# LEDControlSchaltPlan.net
KiCad netlist of a schematic drawn in EAGLE
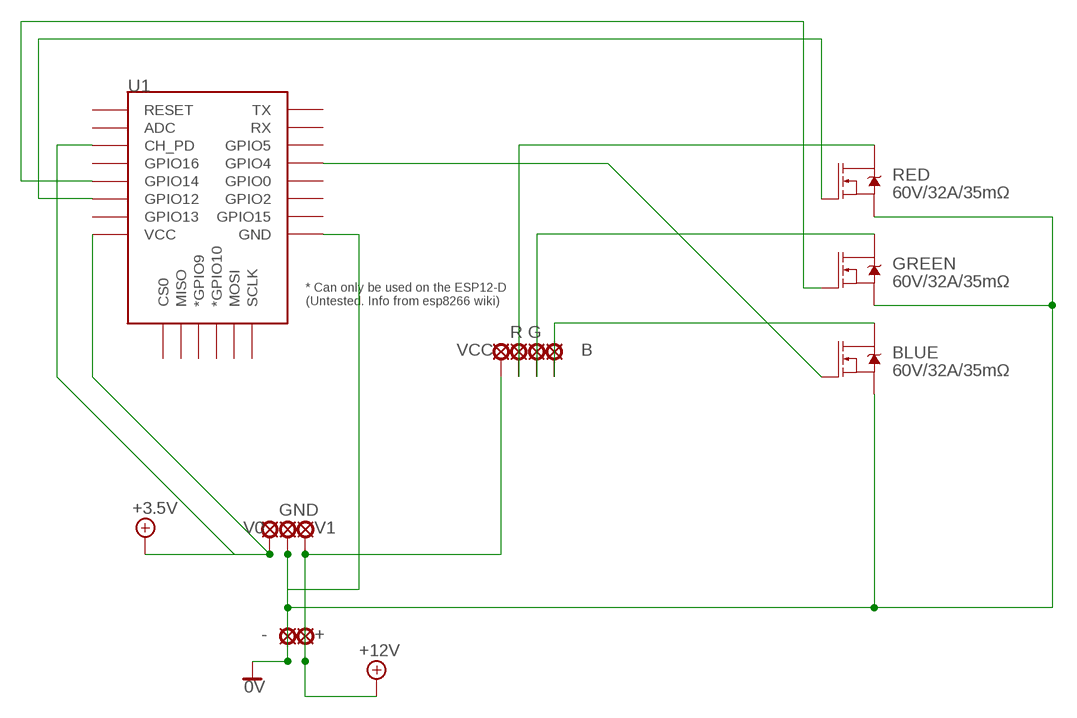
[diagram p0: schematic, sheet 1]

(export (version "E")
  (design (tool "Eeschema 10.0.6"))
  (components
    (comp (ref "+")
      (value "LSP10")
      (footprint "eagle-import:LSP10")
      (libsource (lib "eagle-import") (part "LSP10"))
    )
    (comp (ref "-")
      (value "LSP10")
      (footprint "eagle-import:LSP10")
      (libsource (lib "eagle-import") (part "LSP10"))
    )
    (comp (ref "B")
      (value "LSP10")
      (footprint "eagle-import:LSP10")
      (libsource (lib "eagle-import") (part "LSP10"))
    )
    (comp (ref "BLUE")
      (value "60V/32A/35mΩ")
      (footprint "eagle-import:TO220V")
      (libsource (lib "eagle-import") (part "MOSFET-NCH-FQP30N06L"))
    )
    (comp (ref "G")
      (value "LSP10")
      (footprint "eagle-import:LSP10")
      (libsource (lib "eagle-import") (part "LSP10"))
    )
    (comp (ref "GND")
      (value "LSP10")
      (footprint "eagle-import:LSP10")
      (libsource (lib "eagle-import") (part "LSP10"))
    )
    (comp (ref "GREEN")
      (value "60V/32A/35mΩ")
      (footprint "eagle-import:TO220V")
      (libsource (lib "eagle-import") (part "MOSFET-NCH-FQP30N06L"))
    )
    (comp (ref "R")
      (value "LSP10")
      (footprint "eagle-import:LSP10")
      (libsource (lib "eagle-import") (part "LSP10"))
    )
    (comp (ref "RED")
      (value "60V/32A/35mΩ")
      (footprint "eagle-import:TO220V")
      (libsource (lib "eagle-import") (part "MOSFET-NCH-FQP30N06L"))
    )
    (comp (ref "U1")
      (value "ESP12ESMD")
      (footprint "eagle-import:ESP12E-SMD")
      (libsource (lib "eagle-import") (part "ESP12ESMD"))
    )
    (comp (ref "V0")
      (value "LSP10")
      (footprint "eagle-import:LSP10")
      (libsource (lib "eagle-import") (part "LSP10"))
    )
    (comp (ref "V1")
      (value "LSP10")
      (footprint "eagle-import:LSP10")
      (libsource (lib "eagle-import") (part "LSP10"))
    )
    (comp (ref "VCC")
      (value "LSP10")
      (footprint "eagle-import:LSP10")
      (libsource (lib "eagle-import") (part "LSP10"))
    )
  )
  (nets
    (net (code "1") (name "+3.5V") (class "Default")
      (node (ref "U1") (pin "CH_PD") (pinfunction "CH_PD_CH_PD") (pintype "bidirectional"))
      (node (ref "U1") (pin "VCC") (pinfunction "VCC_VCC") (pintype "bidirectional"))
      (node (ref "V0") (pin "MP") (pinfunction "MP_MP") (pintype "passive"))
    )
    (net (code "2") (name "+12V") (class "Default")
      (node (ref "+") (pin "MP") (pinfunction "MP_MP") (pintype "passive"))
      (node (ref "V1") (pin "MP") (pinfunction "MP_MP") (pintype "passive"))
      (node (ref "VCC") (pin "MP") (pinfunction "MP_MP") (pintype "passive"))
    )
    (net (code "3") (name "0V") (class "Default")
      (node (ref "-") (pin "MP") (pinfunction "MP_MP") (pintype "passive"))
      (node (ref "BLUE") (pin "3") (pinfunction "S_3") (pintype "bidirectional"))
      (node (ref "GND") (pin "MP") (pinfunction "MP_MP") (pintype "passive"))
      (node (ref "GREEN") (pin "3") (pinfunction "S_3") (pintype "bidirectional"))
      (node (ref "RED") (pin "3") (pinfunction "S_3") (pintype "bidirectional"))
      (node (ref "U1") (pin "GND") (pinfunction "GND_GND") (pintype "bidirectional"))
    )
    (net (code "4") (name "Net-(BLUE-D)") (class "Default")
      (node (ref "B") (pin "MP") (pinfunction "MP_MP") (pintype "passive"))
      (node (ref "BLUE") (pin "2") (pinfunction "D_2") (pintype "bidirectional"))
    )
    (net (code "5") (name "Net-(BLUE-G)") (class "Default")
      (node (ref "BLUE") (pin "1") (pinfunction "G_1") (pintype "bidirectional"))
      (node (ref "U1") (pin "GPIO4") (pinfunction "GPIO4_GPIO4") (pintype "bidirectional"))
    )
    (net (code "6") (name "Net-(GREEN-D)") (class "Default")
      (node (ref "G") (pin "MP") (pinfunction "MP_MP") (pintype "passive"))
      (node (ref "GREEN") (pin "2") (pinfunction "D_2") (pintype "bidirectional"))
    )
    (net (code "7") (name "Net-(GREEN-G)") (class "Default")
      (node (ref "GREEN") (pin "1") (pinfunction "G_1") (pintype "bidirectional"))
      (node (ref "U1") (pin "GPIO14") (pinfunction "GPIO14_GPIO14") (pintype "bidirectional"))
    )
    (net (code "8") (name "Net-(RED-D)") (class "Default")
      (node (ref "R") (pin "MP") (pinfunction "MP_MP") (pintype "passive"))
      (node (ref "RED") (pin "2") (pinfunction "D_2") (pintype "bidirectional"))
    )
    (net (code "9") (name "Net-(RED-G)") (class "Default")
      (node (ref "RED") (pin "1") (pinfunction "G_1") (pintype "bidirectional"))
      (node (ref "U1") (pin "GPIO12") (pinfunction "GPIO12_GPIO12") (pintype "bidirectional"))
    )
    (net (code "10") (name "unconnected-(U1-*GPIO9-PadGPIO9)") (class "Default")
      (node (ref "U1") (pin "GPIO9") (pinfunction "*GPIO9_GPIO9") (pintype "bidirectional"))
    )
    (net (code "11") (name "unconnected-(U1-*GPIO10-PadGPIO10)") (class "Default")
      (node (ref "U1") (pin "GPIO10") (pinfunction "*GPIO10_GPIO10") (pintype "bidirectional"))
    )
    (net (code "12") (name "unconnected-(U1-PadADC)") (class "Default")
      (node (ref "U1") (pin "ADC") (pinfunction "ADC_ADC") (pintype "bidirectional"))
    )
    (net (code "13") (name "unconnected-(U1-PadCS0)") (class "Default")
      (node (ref "U1") (pin "CS0") (pinfunction "CS0_CS0") (pintype "bidirectional"))
    )
    (net (code "14") (name "unconnected-(U1-PadGPIO0)") (class "Default")
      (node (ref "U1") (pin "GPIO0") (pinfunction "GPIO0_GPIO0") (pintype "bidirectional"))
    )
    (net (code "15") (name "unconnected-(U1-PadGPIO2)") (class "Default")
      (node (ref "U1") (pin "GPIO2") (pinfunction "GPIO2_GPIO2") (pintype "bidirectional"))
    )
    (net (code "16") (name "unconnected-(U1-PadGPIO5)") (class "Default")
      (node (ref "U1") (pin "GPIO5") (pinfunction "GPIO5_GPIO5") (pintype "bidirectional"))
    )
    (net (code "17") (name "unconnected-(U1-PadGPIO13)") (class "Default")
      (node (ref "U1") (pin "GPIO13") (pinfunction "GPIO13_GPIO13") (pintype "bidirectional"))
    )
    (net (code "18") (name "unconnected-(U1-PadGPIO15)") (class "Default")
      (node (ref "U1") (pin "GPIO15") (pinfunction "GPIO15_GPIO15") (pintype "bidirectional"))
    )
    (net (code "19") (name "unconnected-(U1-PadGPIO16)") (class "Default")
      (node (ref "U1") (pin "GPIO16") (pinfunction "GPIO16_GPIO16") (pintype "bidirectional"))
    )
    (net (code "20") (name "unconnected-(U1-PadMISO)") (class "Default")
      (node (ref "U1") (pin "MISO") (pinfunction "MISO_MISO") (pintype "bidirectional"))
    )
    (net (code "21") (name "unconnected-(U1-PadMOSI)") (class "Default")
      (node (ref "U1") (pin "MOSI") (pinfunction "MOSI_MOSI") (pintype "bidirectional"))
    )
    (net (code "22") (name "unconnected-(U1-PadRESET)") (class "Default")
      (node (ref "U1") (pin "RESET") (pinfunction "RESET_RESET") (pintype "bidirectional"))
    )
    (net (code "23") (name "unconnected-(U1-PadSCLK)") (class "Default")
      (node (ref "U1") (pin "SCLK") (pinfunction "SCLK_SCLK") (pintype "bidirectional"))
    )
    (net (code "24") (name "unconnected-(U1-RX-PadRXD0)") (class "Default")
      (node (ref "U1") (pin "RXD0") (pinfunction "RX_RXD0") (pintype "bidirectional"))
    )
    (net (code "25") (name "unconnected-(U1-TX-PadTXD0)") (class "Default")
      (node (ref "U1") (pin "TXD0") (pinfunction "TX_TXD0") (pintype "bidirectional"))
    )
  )
)
